# PIC_16F877A_Board_V4_SMD.net
KiCad netlist of a schematic drawn in EAGLE
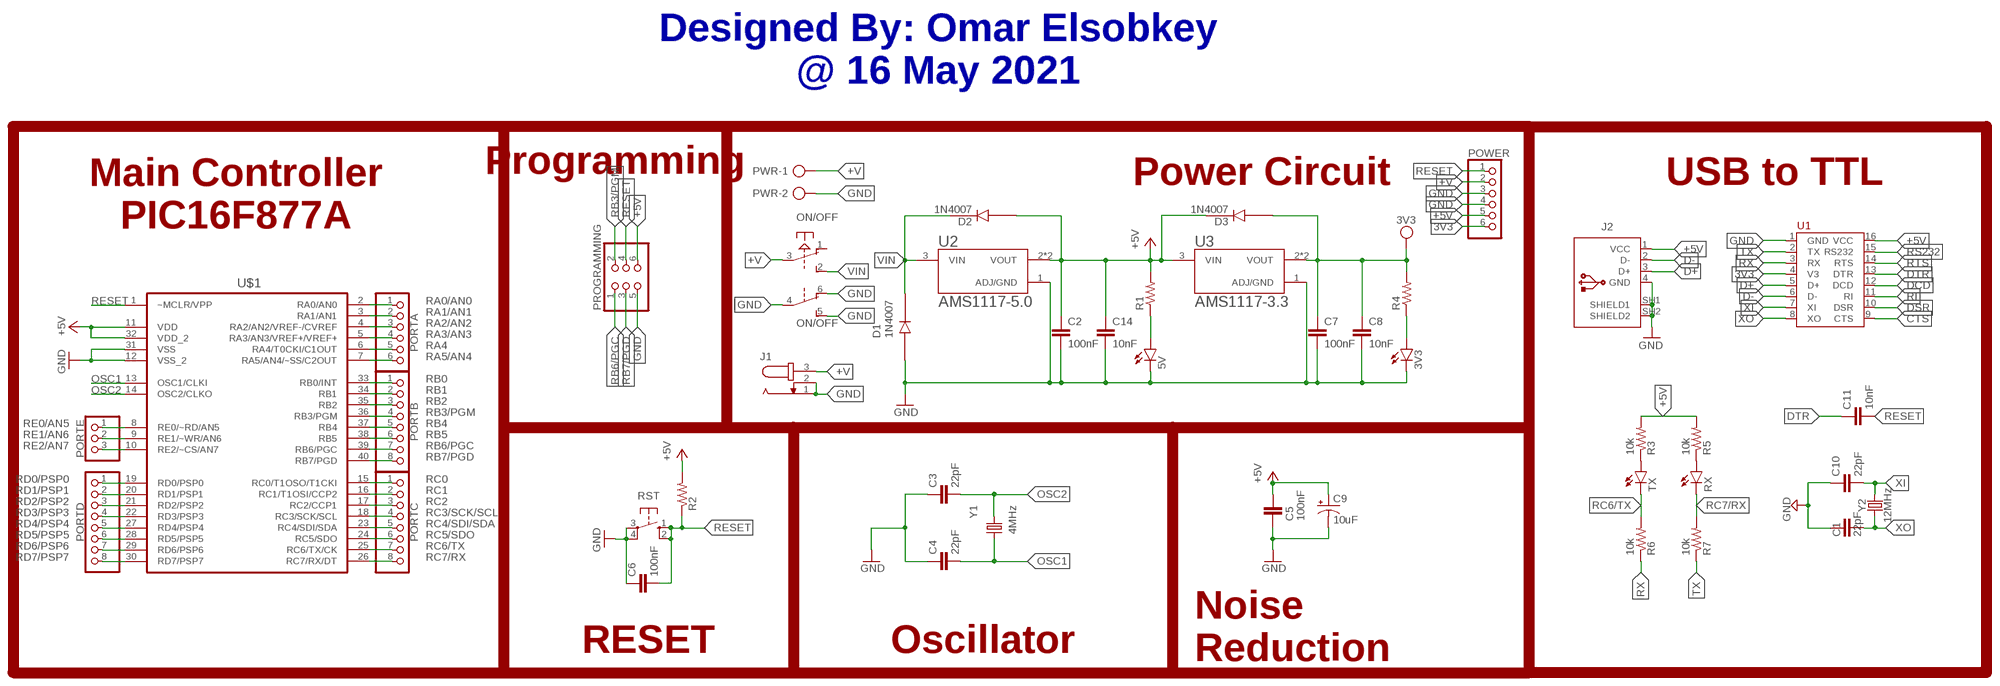
[diagram p0: schematic, sheet 1]

(export (version "E")
  (design (tool "Eeschema 10.0.6"))
  (components
    (comp (ref "3V3")
      (value "LEDSML0805")
      (footprint "eagle-import:SML0805")
      (libsource (lib "eagle-import") (part "LEDSML0805"))
    )
    (comp (ref "5V")
      (value "LEDSML0805")
      (footprint "eagle-import:SML0805")
      (libsource (lib "eagle-import") (part "LEDSML0805"))
    )
    (comp (ref "C1")
      (value "22pF")
      (footprint "eagle-import:CAPC2012X110")
      (libsource (lib "eagle-import") (part "CCHIP-0805(2012-METRIC)_"))
    )
    (comp (ref "C2")
      (value "100nF")
      (footprint "eagle-import:CAPC2012X110")
      (libsource (lib "eagle-import") (part "CCHIP-0805(2012-METRIC)_"))
    )
    (comp (ref "C3")
      (value "22pF")
      (footprint "eagle-import:CAPC2012X110")
      (libsource (lib "eagle-import") (part "CCHIP-0805(2012-METRIC)_"))
    )
    (comp (ref "C4")
      (value "22pF")
      (footprint "eagle-import:CAPC2012X110")
      (libsource (lib "eagle-import") (part "CCHIP-0805(2012-METRIC)_"))
    )
    (comp (ref "C5")
      (value "100nF")
      (footprint "eagle-import:CAPC2012X110")
      (libsource (lib "eagle-import") (part "CCHIP-0805(2012-METRIC)_"))
    )
    (comp (ref "C6")
      (value "100nF")
      (footprint "eagle-import:CAPC2012X110")
      (libsource (lib "eagle-import") (part "CCHIP-0805(2012-METRIC)_"))
    )
    (comp (ref "C7")
      (value "100nF")
      (footprint "eagle-import:CAPC2012X110")
      (libsource (lib "eagle-import") (part "CCHIP-0805(2012-METRIC)_"))
    )
    (comp (ref "C8")
      (value "10nF")
      (footprint "eagle-import:CAPC2012X110")
      (libsource (lib "eagle-import") (part "CCHIP-0805(2012-METRIC)_"))
    )
    (comp (ref "C9")
      (value "10uF")
      (footprint "eagle-import:CPOL-RADIAL-2.5MM-5MM-KIT")
      (libsource (lib "eagle-import") (part "10UF-POLAR-RADIAL-2.5MM-KIT-25V-20%"))
    )
    (comp (ref "C10")
      (value "22pF")
      (footprint "eagle-import:CAPC2012X110")
      (libsource (lib "eagle-import") (part "CCHIP-0805(2012-METRIC)_"))
    )
    (comp (ref "C11")
      (value "10nF")
      (footprint "eagle-import:CAPC2012X110")
      (libsource (lib "eagle-import") (part "CCHIP-0805(2012-METRIC)_"))
    )
    (comp (ref "C14")
      (value "10nF")
      (footprint "eagle-import:CAPC2012X110")
      (libsource (lib "eagle-import") (part "CCHIP-0805(2012-METRIC)_"))
    )
    (comp (ref "D1")
      (value "1N4007")
      (footprint "eagle-import:SMA_DO-214AC")
      (fields (field (name "MF") "NKK Switches") (field (name "MP") "S1A"))
      (libsource (lib "eagle-import") (part "DIODE_SMD"))
    )
    (comp (ref "D2")
      (value "1N4007")
      (footprint "eagle-import:SMA_DO-214AC")
      (fields (field (name "MF") "NKK Switches") (field (name "MP") "S1A"))
      (libsource (lib "eagle-import") (part "DIODE_SMD"))
    )
    (comp (ref "D3")
      (value "1N4007")
      (footprint "eagle-import:SMA_DO-214AC")
      (fields (field (name "MF") "NKK Switches") (field (name "MP") "S1A"))
      (libsource (lib "eagle-import") (part "DIODE_SMD"))
    )
    (comp (ref "J1")
      (value "JACK-PLUG0")
      (footprint "eagle-import:SPC4077")
      (libsource (lib "eagle-import") (part "JACK-PLUG0"))
    )
    (comp (ref "J2")
      (value "61729-1011")
      (footprint "eagle-import:61729-1011BLF")
      (fields (field (name "MANUFACTURER") "Amphenol ICC (FCI)") (field (name "MPN") "61729-1011BLF"))
      (libsource (lib "eagle-import") (part "61729-1011"))
    )
    (comp (ref "ON/OFF")
      (value "PVA2R")
      (footprint "eagle-import:PVA2R")
      (libsource (lib "eagle-import") (part "PVA2R"))
    )
    (comp (ref "PORTA")
      (value "PINHD-1X6")
      (footprint "eagle-import:1X06")
      (libsource (lib "eagle-import") (part "PINHD-1X6"))
    )
    (comp (ref "PORTB")
      (value "PINHD-1X8")
      (footprint "eagle-import:1X08")
      (libsource (lib "eagle-import") (part "PINHD-1X8"))
    )
    (comp (ref "PORTC")
      (value "PINHD-1X8")
      (footprint "eagle-import:1X08")
      (libsource (lib "eagle-import") (part "PINHD-1X8"))
    )
    (comp (ref "PORTD")
      (value "PINHD-1X8")
      (footprint "eagle-import:1X08")
      (libsource (lib "eagle-import") (part "PINHD-1X8"))
    )
    (comp (ref "PORTE")
      (value "PINHD-1X3")
      (footprint "eagle-import:1X03")
      (libsource (lib "eagle-import") (part "PINHD-1X3"))
    )
    (comp (ref "POWER")
      (value "PINHD-1X6")
      (footprint "eagle-import:1X06")
      (libsource (lib "eagle-import") (part "PINHD-1X6"))
    )
    (comp (ref "PROGRAMMING")
      (value "PINHD-2X3")
      (footprint "eagle-import:2X03")
      (libsource (lib "eagle-import") (part "PINHD-2X3"))
    )
    (comp (ref "PWR")
      (value "AK500/2-H")
      (footprint "eagle-import:AK500_2-H")
      (libsource (lib "eagle-import") (part "AK500/2-H"))
    )
    (comp (ref "R1")
      (value "RESISTOR1206")
      (footprint "eagle-import:1206")
      (libsource (lib "eagle-import") (part "RESISTOR1206"))
    )
    (comp (ref "R2")
      (value "RESISTOR1206")
      (footprint "eagle-import:1206")
      (libsource (lib "eagle-import") (part "RESISTOR1206"))
    )
    (comp (ref "R3")
      (value "10k")
      (footprint "eagle-import:1206")
      (libsource (lib "eagle-import") (part "RESISTOR1206"))
    )
    (comp (ref "R4")
      (value "RESISTOR1206")
      (footprint "eagle-import:1206")
      (libsource (lib "eagle-import") (part "RESISTOR1206"))
    )
    (comp (ref "R5")
      (value "10k")
      (footprint "eagle-import:1206")
      (libsource (lib "eagle-import") (part "RESISTOR1206"))
    )
    (comp (ref "R6")
      (value "10k")
      (footprint "eagle-import:1206")
      (libsource (lib "eagle-import") (part "RESISTOR1206"))
    )
    (comp (ref "R7")
      (value "10k")
      (footprint "eagle-import:1206")
      (libsource (lib "eagle-import") (part "RESISTOR1206"))
    )
    (comp (ref "RST")
      (value "10-XX")
      (footprint "eagle-import:B3F-10XX")
      (fields (field (name "MPN") "B3F-1000"))
      (libsource (lib "eagle-import") (part "10-XX"))
    )
    (comp (ref "RX")
      (value "LEDSML0805")
      (footprint "eagle-import:SML0805")
      (libsource (lib "eagle-import") (part "LEDSML0805"))
    )
    (comp (ref "TX")
      (value "LEDSML0805")
      (footprint "eagle-import:SML0805")
      (libsource (lib "eagle-import") (part "LEDSML0805"))
    )
    (comp (ref "U$1")
      (value "PIC16F877A-I/P")
      (footprint "eagle-import:PDIP-40")
      (fields (field (name "MF") "Microchip"))
      (libsource (lib "eagle-import") (part "PIC16F877A-I/P"))
    )
    (comp (ref "U1")
      (value "CH340G")
      (footprint "eagle-import:SOP-16")
      (libsource (lib "eagle-import") (part "CH340G"))
    )
    (comp (ref "U2")
      (value "AMS1117-5.0")
      (footprint "eagle-import:AMS1117-5.0")
      (fields (field (name "MF") "Advanced Monolithic Systems"))
      (libsource (lib "eagle-import") (part "AMS1117-5.0"))
    )
    (comp (ref "U3")
      (value "AMS1117-3.3")
      (footprint "eagle-import:AMS1117-5.0")
      (fields (field (name "MF") "Advanced Monolithic Systems") (field (name "MP") "AMS1117-5.0"))
      (libsource (lib "eagle-import") (part "AMS1117-5.0"))
    )
    (comp (ref "Y1")
      (value "4MHz")
      (footprint "eagle-import:HC49U")
      (libsource (lib "eagle-import") (part "CRYSTALPTH-HC49UV"))
    )
    (comp (ref "Y2")
      (value "12MHz")
      (footprint "eagle-import:HC49U")
      (libsource (lib "eagle-import") (part "CRYSTALPTH-HC49UV"))
    )
  )
  (nets
    (net (code "1") (name "+5V") (class "Default")
      (node (ref "C14") (pin "1") (pinfunction "1_1") (pintype "passive"))
      (node (ref "C2") (pin "1") (pinfunction "1_1") (pintype "passive"))
      (node (ref "C5") (pin "2") (pinfunction "2_2") (pintype "passive"))
      (node (ref "C9") (pin "1") (pinfunction "+_1") (pintype "passive"))
      (node (ref "D2") (pin "2") (pinfunction "A_2") (pintype "passive"))
      (node (ref "D3") (pin "1") (pinfunction "C_1") (pintype "passive"))
      (node (ref "J2") (pin "1") (pinfunction "VCC_1") (pintype "power_in"))
      (node (ref "POWER") (pin "5") (pinfunction "5_5") (pintype "passive"))
      (node (ref "PROGRAMMING") (pin "6") (pinfunction "6_6") (pintype "passive"))
      (node (ref "R1") (pin "2") (pinfunction "2_2") (pintype "passive"))
      (node (ref "R2") (pin "2") (pinfunction "2_2") (pintype "passive"))
      (node (ref "R3") (pin "2") (pinfunction "2_2") (pintype "passive"))
      (node (ref "R5") (pin "2") (pinfunction "2_2") (pintype "passive"))
      (node (ref "U$1") (pin "11") (pinfunction "VDD_11") (pintype "power_in"))
      (node (ref "U$1") (pin "32") (pinfunction "VDD_2_32") (pintype "power_in"))
      (node (ref "U1") (pin "16") (pinfunction "VCC_16") (pintype "bidirectional"))
      (node (ref "U2") (pin "2") (pinfunction "VOUT_2") (pintype "output"))
      (node (ref "U2") (pin "4") (pinfunction "VOUT_4") (pintype "output"))
      (node (ref "U3") (pin "3") (pinfunction "VIN_3") (pintype "input"))
    )
    (net (code "2") (name "+V") (class "Default")
      (node (ref "J1") (pin "3") (pinfunction "3_3") (pintype "passive"))
      (node (ref "ON/OFF") (pin "3") (pinfunction "P_3") (pintype "passive"))
      (node (ref "POWER") (pin "2") (pinfunction "2_2") (pintype "passive"))
      (node (ref "PWR") (pin "1") (pinfunction "KL_1") (pintype "passive"))
    )
    (net (code "3") (name "/RA0{slash}AN0") (class "Default")
      (node (ref "PORTA") (pin "1") (pinfunction "1_1") (pintype "passive"))
      (node (ref "U$1") (pin "2") (pinfunction "RA0/AN0_2") (pintype "bidirectional"))
    )
    (net (code "4") (name "/RA1{slash}AN1") (class "Default")
      (node (ref "PORTA") (pin "2") (pinfunction "2_2") (pintype "passive"))
      (node (ref "U$1") (pin "3") (pinfunction "RA1/AN1_3") (pintype "bidirectional"))
    )
    (net (code "5") (name "/RA2{slash}AN2") (class "Default")
      (node (ref "PORTA") (pin "3") (pinfunction "3_3") (pintype "passive"))
      (node (ref "U$1") (pin "4") (pinfunction "RA2/AN2/VREF-/CVREF_4") (pintype "bidirectional"))
    )
    (net (code "6") (name "/RA3{slash}AN3") (class "Default")
      (node (ref "PORTA") (pin "4") (pinfunction "4_4") (pintype "passive"))
      (node (ref "U$1") (pin "5") (pinfunction "RA3/AN3/VREF+/VREF+_5") (pintype "bidirectional"))
    )
    (net (code "7") (name "/RA4") (class "Default")
      (node (ref "PORTA") (pin "5") (pinfunction "5_5") (pintype "passive"))
      (node (ref "U$1") (pin "6") (pinfunction "RA4/T0CKI/C1OUT_6") (pintype "bidirectional"))
    )
    (net (code "8") (name "/RA5{slash}AN4") (class "Default")
      (node (ref "PORTA") (pin "6") (pinfunction "6_6") (pintype "passive"))
      (node (ref "U$1") (pin "7") (pinfunction "RA5/AN4/~{SS/C2OUT}_7") (pintype "bidirectional"))
    )
    (net (code "9") (name "/RB0") (class "Default")
      (node (ref "PORTB") (pin "1") (pinfunction "1_1") (pintype "passive"))
      (node (ref "U$1") (pin "33") (pinfunction "RB0/INT_33") (pintype "bidirectional"))
    )
    (net (code "10") (name "/RB1") (class "Default")
      (node (ref "PORTB") (pin "2") (pinfunction "2_2") (pintype "passive"))
      (node (ref "U$1") (pin "34") (pinfunction "RB1_34") (pintype "bidirectional"))
    )
    (net (code "11") (name "/RB2") (class "Default")
      (node (ref "PORTB") (pin "3") (pinfunction "3_3") (pintype "passive"))
      (node (ref "U$1") (pin "35") (pinfunction "RB2_35") (pintype "bidirectional"))
    )
    (net (code "12") (name "/RB4") (class "Default")
      (node (ref "PORTB") (pin "5") (pinfunction "5_5") (pintype "passive"))
      (node (ref "U$1") (pin "37") (pinfunction "RB4_37") (pintype "bidirectional"))
    )
    (net (code "13") (name "/RB5") (class "Default")
      (node (ref "PORTB") (pin "6") (pinfunction "6_6") (pintype "passive"))
      (node (ref "U$1") (pin "38") (pinfunction "RB5_38") (pintype "bidirectional"))
    )
    (net (code "14") (name "/RC0") (class "Default")
      (node (ref "PORTC") (pin "1") (pinfunction "1_1") (pintype "passive"))
      (node (ref "U$1") (pin "15") (pinfunction "RC0/T1OSO/T1CKI_15") (pintype "bidirectional"))
    )
    (net (code "15") (name "/RC1") (class "Default")
      (node (ref "PORTC") (pin "2") (pinfunction "2_2") (pintype "passive"))
      (node (ref "U$1") (pin "16") (pinfunction "RC1/T1OSI/CCP2_16") (pintype "bidirectional"))
    )
    (net (code "16") (name "/RC2") (class "Default")
      (node (ref "PORTC") (pin "3") (pinfunction "3_3") (pintype "passive"))
      (node (ref "U$1") (pin "17") (pinfunction "RC2/CCP1_17") (pintype "bidirectional"))
    )
    (net (code "17") (name "/RC3{slash}SCK{slash}SCL") (class "Default")
      (node (ref "PORTC") (pin "4") (pinfunction "4_4") (pintype "passive"))
      (node (ref "U$1") (pin "18") (pinfunction "RC3/SCK/SCL_18") (pintype "bidirectional"))
    )
    (net (code "18") (name "/RC4{slash}SDI{slash}SDA") (class "Default")
      (node (ref "PORTC") (pin "5") (pinfunction "5_5") (pintype "passive"))
      (node (ref "U$1") (pin "23") (pinfunction "RC4/SDI/SDA_23") (pintype "bidirectional"))
    )
    (net (code "19") (name "/RC5{slash}SDO") (class "Default")
      (node (ref "PORTC") (pin "6") (pinfunction "6_6") (pintype "passive"))
      (node (ref "U$1") (pin "24") (pinfunction "RC5/SDO_24") (pintype "bidirectional"))
    )
    (net (code "20") (name "/RD0{slash}PSP0") (class "Default")
      (node (ref "PORTD") (pin "1") (pinfunction "1_1") (pintype "passive"))
      (node (ref "U$1") (pin "19") (pinfunction "RD0/PSP0_19") (pintype "bidirectional"))
    )
    (net (code "21") (name "/RD1{slash}PSP1") (class "Default")
      (node (ref "PORTD") (pin "2") (pinfunction "2_2") (pintype "passive"))
      (node (ref "U$1") (pin "20") (pinfunction "RD1/PSP1_20") (pintype "bidirectional"))
    )
    (net (code "22") (name "/RD2{slash}PSP2") (class "Default")
      (node (ref "PORTD") (pin "3") (pinfunction "3_3") (pintype "passive"))
      (node (ref "U$1") (pin "21") (pinfunction "RD2/PSP2_21") (pintype "bidirectional"))
    )
    (net (code "23") (name "/RD3{slash}PSP3") (class "Default")
      (node (ref "PORTD") (pin "4") (pinfunction "4_4") (pintype "passive"))
      (node (ref "U$1") (pin "22") (pinfunction "RD3/PSP3_22") (pintype "bidirectional"))
    )
    (net (code "24") (name "/RD4{slash}PSP4") (class "Default")
      (node (ref "PORTD") (pin "5") (pinfunction "5_5") (pintype "passive"))
      (node (ref "U$1") (pin "27") (pinfunction "RD4/PSP4_27") (pintype "bidirectional"))
    )
    (net (code "25") (name "/RD5{slash}PSP5") (class "Default")
      (node (ref "PORTD") (pin "6") (pinfunction "6_6") (pintype "passive"))
      (node (ref "U$1") (pin "28") (pinfunction "RD5/PSP5_28") (pintype "bidirectional"))
    )
    (net (code "26") (name "/RD6{slash}PSP6") (class "Default")
      (node (ref "PORTD") (pin "7") (pinfunction "7_7") (pintype "passive"))
      (node (ref "U$1") (pin "29") (pinfunction "RD6/PSP6_29") (pintype "bidirectional"))
    )
    (net (code "27") (name "/RD7{slash}PSP7") (class "Default")
      (node (ref "PORTD") (pin "8") (pinfunction "8_8") (pintype "passive"))
      (node (ref "U$1") (pin "30") (pinfunction "RD7/PSP7_30") (pintype "bidirectional"))
    )
    (net (code "28") (name "/RE0{slash}AN5") (class "Default")
      (node (ref "PORTE") (pin "1") (pinfunction "1_1") (pintype "passive"))
      (node (ref "U$1") (pin "8") (pinfunction "RE0/~{RD/AN5}_8") (pintype "bidirectional"))
    )
    (net (code "29") (name "/RE1{slash}AN6") (class "Default")
      (node (ref "PORTE") (pin "2") (pinfunction "2_2") (pintype "passive"))
      (node (ref "U$1") (pin "9") (pinfunction "RE1/~{WR/AN6}_9") (pintype "bidirectional"))
    )
    (net (code "30") (name "/RE2{slash}AN7") (class "Default")
      (node (ref "PORTE") (pin "3") (pinfunction "3_3") (pintype "passive"))
      (node (ref "U$1") (pin "10") (pinfunction "RE2/~{CS/AN7}_10") (pintype "bidirectional"))
    )
    (net (code "31") (name "3V3") (class "Default")
      (node (ref "C7") (pin "1") (pinfunction "1_1") (pintype "passive"))
      (node (ref "C8") (pin "1") (pinfunction "1_1") (pintype "passive"))
      (node (ref "D3") (pin "2") (pinfunction "A_2") (pintype "passive"))
      (node (ref "POWER") (pin "6") (pinfunction "6_6") (pintype "passive"))
      (node (ref "R4") (pin "2") (pinfunction "2_2") (pintype "passive"))
      (node (ref "U1") (pin "4") (pinfunction "V3_4") (pintype "bidirectional"))
      (node (ref "U3") (pin "2") (pinfunction "VOUT_2") (pintype "output"))
      (node (ref "U3") (pin "4") (pinfunction "VOUT_4") (pintype "output"))
    )
    (net (code "32") (name "CTS") (class "Default")
      (node (ref "U1") (pin "9") (pinfunction "CTS_9") (pintype "bidirectional"))
    )
    (net (code "33") (name "D+") (class "Default")
      (node (ref "J2") (pin "3") (pinfunction "D+_3") (pintype "bidirectional"))
      (node (ref "U1") (pin "5") (pinfunction "D+_5") (pintype "bidirectional"))
    )
    (net (code "34") (name "D-") (class "Default")
      (node (ref "J2") (pin "2") (pinfunction "D-_2") (pintype "bidirectional"))
      (node (ref "U1") (pin "6") (pinfunction "D-_6") (pintype "bidirectional"))
    )
    (net (code "35") (name "DCD") (class "Default")
      (node (ref "U1") (pin "12") (pinfunction "DCD_12") (pintype "bidirectional"))
    )
    (net (code "36") (name "DSR") (class "Default")
      (node (ref "U1") (pin "10") (pinfunction "DSR_10") (pintype "bidirectional"))
    )
    (net (code "37") (name "DTR") (class "Default")
      (node (ref "C11") (pin "1") (pinfunction "1_1") (pintype "passive"))
      (node (ref "U1") (pin "13") (pinfunction "DTR_13") (pintype "bidirectional"))
    )
    (net (code "38") (name "GND") (class "Default")
      (node (ref "3V3") (pin "C") (pinfunction "C_C") (pintype "passive"))
      (node (ref "5V") (pin "C") (pinfunction "C_C") (pintype "passive"))
      (node (ref "C1") (pin "1") (pinfunction "1_1") (pintype "passive"))
      (node (ref "C10") (pin "1") (pinfunction "1_1") (pintype "passive"))
      (node (ref "C14") (pin "2") (pinfunction "2_2") (pintype "passive"))
      (node (ref "C2") (pin "2") (pinfunction "2_2") (pintype "passive"))
      (node (ref "C3") (pin "1") (pinfunction "1_1") (pintype "passive"))
      (node (ref "C4") (pin "1") (pinfunction "1_1") (pintype "passive"))
      (node (ref "C5") (pin "1") (pinfunction "1_1") (pintype "passive"))
      (node (ref "C6") (pin "1") (pinfunction "1_1") (pintype "passive"))
      (node (ref "C7") (pin "2") (pinfunction "2_2") (pintype "passive"))
      (node (ref "C8") (pin "2") (pinfunction "2_2") (pintype "passive"))
      (node (ref "C9") (pin "2") (pinfunction "-_2") (pintype "passive"))
      (node (ref "D1") (pin "2") (pinfunction "A_2") (pintype "passive"))
      (node (ref "J1") (pin "1") (pinfunction "1_1") (pintype "passive"))
      (node (ref "J1") (pin "2") (pinfunction "2_2") (pintype "passive"))
      (node (ref "J2") (pin "4") (pinfunction "GND_4") (pintype "power_in"))
      (node (ref "J2") (pin "SH1") (pinfunction "SHIELD1_SH1") (pintype "power_in"))
      (node (ref "J2") (pin "SH2") (pinfunction "SHIELD2_SH2") (pintype "power_in"))
      (node (ref "ON/OFF") (pin "4") (pinfunction "P_4") (pintype "passive"))
      (node (ref "ON/OFF") (pin "5") (pinfunction "S_5") (pintype "passive"))
      (node (ref "ON/OFF") (pin "6") (pinfunction "O_6") (pintype "passive"))
      (node (ref "POWER") (pin "3") (pinfunction "3_3") (pintype "passive"))
      (node (ref "POWER") (pin "4") (pinfunction "4_4") (pintype "passive"))
      (node (ref "PROGRAMMING") (pin "5") (pinfunction "5_5") (pintype "passive"))
      (node (ref "PWR") (pin "2") (pinfunction "KL_2") (pintype "passive"))
      (node (ref "RST") (pin "3") (pinfunction "P_3") (pintype "passive"))
      (node (ref "RST") (pin "4") (pinfunction "P1_4") (pintype "passive"))
      (node (ref "U$1") (pin "12") (pinfunction "VSS_2_12") (pintype "power_in"))
      (node (ref "U$1") (pin "31") (pinfunction "VSS_31") (pintype "power_in"))
      (node (ref "U1") (pin "1") (pinfunction "GND_1") (pintype "bidirectional"))
      (node (ref "U2") (pin "1") (pinfunction "ADJ/GND_1") (pintype "power_in"))
      (node (ref "U3") (pin "1") (pinfunction "ADJ/GND_1") (pintype "power_in"))
    )
    (net (code "39") (name "Net-(3V3-PadA)") (class "Default")
      (node (ref "3V3") (pin "A") (pinfunction "A_A") (pintype "passive"))
      (node (ref "R4") (pin "1") (pinfunction "1_1") (pintype "passive"))
    )
    (net (code "40") (name "Net-(5V-PadA)") (class "Default")
      (node (ref "5V") (pin "A") (pinfunction "A_A") (pintype "passive"))
      (node (ref "R1") (pin "1") (pinfunction "1_1") (pintype "passive"))
    )
    (net (code "41") (name "Net-(R3-Pad1)") (class "Default")
      (node (ref "R3") (pin "1") (pinfunction "1_1") (pintype "passive"))
      (node (ref "TX") (pin "A") (pinfunction "A_A") (pintype "passive"))
    )
    (net (code "42") (name "Net-(R5-Pad1)") (class "Default")
      (node (ref "R5") (pin "1") (pinfunction "1_1") (pintype "passive"))
      (node (ref "RX") (pin "A") (pinfunction "A_A") (pintype "passive"))
    )
    (net (code "43") (name "OSC1") (class "Default")
      (node (ref "C4") (pin "2") (pinfunction "2_2") (pintype "passive"))
      (node (ref "U$1") (pin "13") (pinfunction "OSC1/CLKI_13") (pintype "input"))
      (node (ref "Y1") (pin "2") (pinfunction "2_2") (pintype "passive"))
    )
    (net (code "44") (name "OSC2") (class "Default")
      (node (ref "C3") (pin "2") (pinfunction "2_2") (pintype "passive"))
      (node (ref "U$1") (pin "14") (pinfunction "OSC2/CLKO_14") (pintype "output"))
      (node (ref "Y1") (pin "1") (pinfunction "1_1") (pintype "passive"))
    )
    (net (code "45") (name "RB3{slash}PGM") (class "Default")
      (node (ref "PORTB") (pin "4") (pinfunction "4_4") (pintype "passive"))
      (node (ref "PROGRAMMING") (pin "2") (pinfunction "2_2") (pintype "passive"))
      (node (ref "U$1") (pin "36") (pinfunction "RB3/PGM_36") (pintype "bidirectional"))
    )
    (net (code "46") (name "RB6{slash}PGC") (class "Default")
      (node (ref "PORTB") (pin "7") (pinfunction "7_7") (pintype "passive"))
      (node (ref "PROGRAMMING") (pin "1") (pinfunction "1_1") (pintype "passive"))
      (node (ref "U$1") (pin "39") (pinfunction "RB6/PGC_39") (pintype "bidirectional"))
    )
    (net (code "47") (name "RB7{slash}PGD") (class "Default")
      (node (ref "PORTB") (pin "8") (pinfunction "8_8") (pintype "passive"))
      (node (ref "PROGRAMMING") (pin "3") (pinfunction "3_3") (pintype "passive"))
      (node (ref "U$1") (pin "40") (pinfunction "RB7/PGD_40") (pintype "bidirectional"))
    )
    (net (code "48") (name "RC6{slash}TX") (class "Default")
      (node (ref "PORTC") (pin "7") (pinfunction "7_7") (pintype "passive"))
      (node (ref "R6") (pin "2") (pinfunction "2_2") (pintype "passive"))
      (node (ref "TX") (pin "C") (pinfunction "C_C") (pintype "passive"))
      (node (ref "U$1") (pin "25") (pinfunction "RC6/TX/CK_25") (pintype "bidirectional"))
    )
    (net (code "49") (name "RC7{slash}RX") (class "Default")
      (node (ref "PORTC") (pin "8") (pinfunction "8_8") (pintype "passive"))
      (node (ref "R7") (pin "2") (pinfunction "2_2") (pintype "passive"))
      (node (ref "RX") (pin "C") (pinfunction "C_C") (pintype "passive"))
      (node (ref "U$1") (pin "26") (pinfunction "RC7/RX/DT_26") (pintype "bidirectional"))
    )
    (net (code "50") (name "RESET") (class "Default")
      (node (ref "C11") (pin "2") (pinfunction "2_2") (pintype "passive"))
      (node (ref "C6") (pin "2") (pinfunction "2_2") (pintype "passive"))
      (node (ref "POWER") (pin "1") (pinfunction "1_1") (pintype "passive"))
      (node (ref "PROGRAMMING") (pin "4") (pinfunction "4_4") (pintype "passive"))
      (node (ref "R2") (pin "1") (pinfunction "1_1") (pintype "passive"))
      (node (ref "RST") (pin "1") (pinfunction "S_1") (pintype "passive"))
      (node (ref "RST") (pin "2") (pinfunction "S1_2") (pintype "passive"))
      (node (ref "U$1") (pin "1") (pinfunction "~{MCLR/VPP}_1") (pintype "input"))
    )
    (net (code "51") (name "RI") (class "Default")
      (node (ref "U1") (pin "11") (pinfunction "RI_11") (pintype "bidirectional"))
    )
    (net (code "52") (name "RS232") (class "Default")
      (node (ref "U1") (pin "15") (pinfunction "RS232_15") (pintype "bidirectional"))
    )
    (net (code "53") (name "RTS") (class "Default")
      (node (ref "U1") (pin "14") (pinfunction "RTS_14") (pintype "bidirectional"))
    )
    (net (code "54") (name "RX") (class "Default")
      (node (ref "R6") (pin "1") (pinfunction "1_1") (pintype "passive"))
      (node (ref "U1") (pin "3") (pinfunction "RX_3") (pintype "bidirectional"))
    )
    (net (code "55") (name "TX") (class "Default")
      (node (ref "R7") (pin "1") (pinfunction "1_1") (pintype "passive"))
      (node (ref "U1") (pin "2") (pinfunction "TX_2") (pintype "bidirectional"))
    )
    (net (code "56") (name "VIN") (class "Default")
      (node (ref "D1") (pin "1") (pinfunction "C_1") (pintype "passive"))
      (node (ref "D2") (pin "1") (pinfunction "C_1") (pintype "passive"))
      (node (ref "ON/OFF") (pin "2") (pinfunction "S_2") (pintype "passive"))
      (node (ref "U2") (pin "3") (pinfunction "VIN_3") (pintype "input"))
    )
    (net (code "57") (name "XI") (class "Default")
      (node (ref "C10") (pin "2") (pinfunction "2_2") (pintype "passive"))
      (node (ref "U1") (pin "7") (pinfunction "XI_7") (pintype "bidirectional"))
      (node (ref "Y2") (pin "2") (pinfunction "2_2") (pintype "passive"))
    )
    (net (code "58") (name "XO") (class "Default")
      (node (ref "C1") (pin "2") (pinfunction "2_2") (pintype "passive"))
      (node (ref "U1") (pin "8") (pinfunction "XO_8") (pintype "bidirectional"))
      (node (ref "Y2") (pin "1") (pinfunction "1_1") (pintype "passive"))
    )
    (net (code "59") (name "unconnected-(ON/OFFA-O-Pad1)") (class "Default")
      (node (ref "ON/OFF") (pin "1") (pinfunction "O_1") (pintype "passive"))
    )
  )
)
